# 14-Bit_ADC.net
KiCad netlist of a schematic drawn in Altium Designer
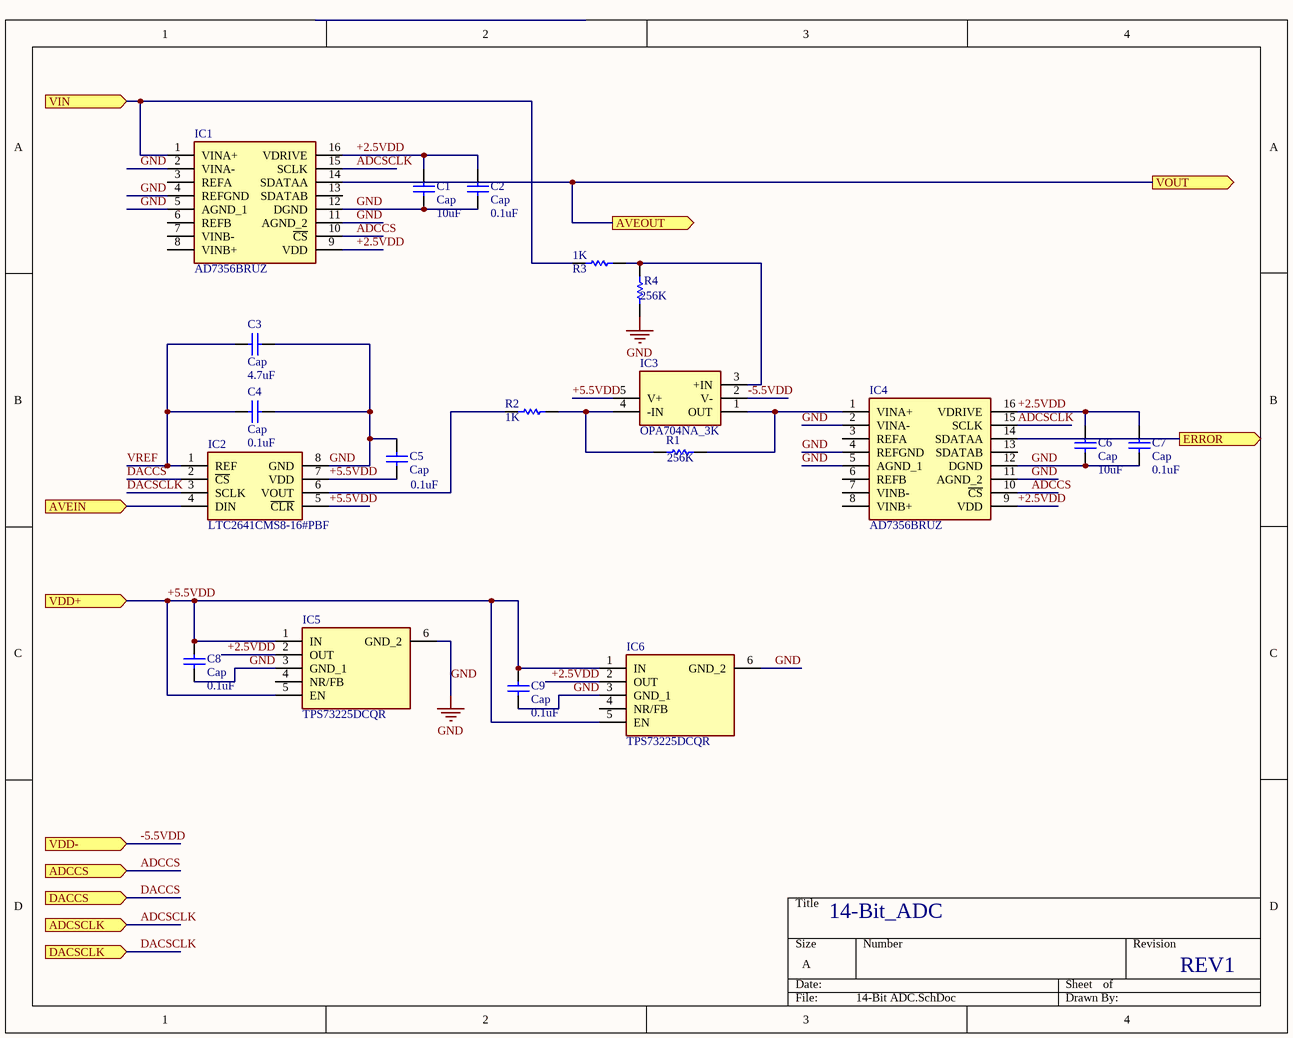
[diagram p0: 14-Bit ADC.SchDoc]

(export (version "E")
  (design (tool "Eeschema 10.0.6"))
  (components
    (comp (ref "C1")
      (value "Cap")
      (footprint "RAD-0.3")
      (description "Capacitor")
      (fields (field (name "ALTIUM_VALUE") "10uF") (field (name "PUBLISHER") "Altium Limited"))
      (libsource (lib "Miscellaneous Devices") (part "Cap"))
    )
    (comp (ref "C2")
      (value "Cap")
      (footprint "RAD-0.3")
      (description "Capacitor")
      (fields (field (name "ALTIUM_VALUE") "0.1uF") (field (name "PUBLISHER") "Altium Limited"))
      (libsource (lib "Miscellaneous Devices") (part "Cap"))
    )
    (comp (ref "C3")
      (value "Cap")
      (footprint "RAD-0.3")
      (description "Capacitor")
      (fields (field (name "ALTIUM_VALUE") "4.7uF") (field (name "PUBLISHER") "Altium Limited"))
      (libsource (lib "Miscellaneous Devices") (part "Cap"))
    )
    (comp (ref "C4")
      (value "Cap")
      (footprint "RAD-0.3")
      (description "Capacitor")
      (fields (field (name "ALTIUM_VALUE") "0.1uF") (field (name "PUBLISHER") "Altium Limited"))
      (libsource (lib "Miscellaneous Devices") (part "Cap"))
    )
    (comp (ref "C5")
      (value "Cap")
      (footprint "RAD-0.3")
      (description "Capacitor")
      (fields (field (name "ALTIUM_VALUE") "0.1uF") (field (name "PUBLISHER") "Altium Limited"))
      (libsource (lib "Miscellaneous Devices") (part "Cap"))
    )
    (comp (ref "C6")
      (value "Cap")
      (footprint "RAD-0.3")
      (description "Capacitor")
      (fields (field (name "ALTIUM_VALUE") "10uF") (field (name "PUBLISHER") "Altium Limited"))
      (libsource (lib "Miscellaneous Devices") (part "Cap"))
    )
    (comp (ref "C7")
      (value "Cap")
      (footprint "RAD-0.3")
      (description "Capacitor")
      (fields (field (name "ALTIUM_VALUE") "0.1uF") (field (name "PUBLISHER") "Altium Limited"))
      (libsource (lib "Miscellaneous Devices") (part "Cap"))
    )
    (comp (ref "C8")
      (value "Cap")
      (footprint "RAD-0.3")
      (description "Capacitor")
      (fields (field (name "ALTIUM_VALUE") "0.1uF") (field (name "PUBLISHER") "Altium Limited"))
      (libsource (lib "Miscellaneous Devices") (part "Cap"))
    )
    (comp (ref "C9")
      (value "Cap")
      (footprint "RAD-0.3")
      (description "Capacitor")
      (fields (field (name "ALTIUM_VALUE") "0.1uF") (field (name "PUBLISHER") "Altium Limited"))
      (libsource (lib "Miscellaneous Devices") (part "Cap"))
    )
    (comp (ref "IC1")
      (value "AD7356BRUZ")
      (footprint "SamacSys:SOP65P640X120-16N")
      (description "Integrated Circuit")
      (libsource (lib "*") (part "AD7356BRUZ"))
    )
    (comp (ref "IC2")
      (value "LTC2641CMS8-16#PBF")
      (footprint "SamacSys:SOP65P490X110-8N")
      (description "Integrated Circuit")
      (fields (field (name "MOUSER PART NUMBER") "584-C2641CMS8-16PBF"))
      (libsource (lib "*") (part "LTC2641CMS8-16#PBF"))
    )
    (comp (ref "IC3")
      (value "OPA704NA_3K")
      (footprint "SamacSys:SOT95P280X145-5N")
      (description "Integrated Circuit")
      (fields (field (name "MANUFACTURER_PART_NUMBER") "OPA704NA/3K"))
      (libsource (lib "*") (part "OPA704NA_3K"))
    )
    (comp (ref "IC4")
      (value "AD7356BRUZ")
      (footprint "SamacSys:SOP65P640X120-16N")
      (description "Integrated Circuit")
      (libsource (lib "*") (part "AD7356BRUZ"))
    )
    (comp (ref "IC5")
      (value "TPS73225DCQR")
      (footprint "SamacSys:SOT127P706X180-6N")
      (description "Integrated Circuit")
      (libsource (lib "*") (part "TPS73225DCQR"))
    )
    (comp (ref "IC6")
      (value "TPS73225DCQR")
      (footprint "SamacSys:SOT127P706X180-6N")
      (description "Integrated Circuit")
      (libsource (lib "*") (part "TPS73225DCQR"))
    )
    (comp (ref "R1")
      (value "256K")
      (footprint "AXIAL-0.3")
      (description "Resistor")
      (fields (field (name "PUBLISHER") "Altium Limited"))
      (libsource (lib "Miscellaneous Devices") (part "Res1"))
    )
    (comp (ref "R2")
      (value "1K")
      (footprint "AXIAL-0.3")
      (description "Resistor")
      (fields (field (name "PUBLISHER") "Altium Limited"))
      (libsource (lib "Miscellaneous Devices") (part "Res1"))
    )
    (comp (ref "R3")
      (value "1K")
      (footprint "AXIAL-0.3")
      (description "Resistor")
      (fields (field (name "PUBLISHER") "Altium Limited"))
      (libsource (lib "Miscellaneous Devices") (part "Res1"))
    )
    (comp (ref "R4")
      (value "256K")
      (footprint "AXIAL-0.3")
      (description "Resistor")
      (fields (field (name "PUBLISHER") "Altium Limited"))
      (libsource (lib "Miscellaneous Devices") (part "Res1"))
    )
  )
  (nets
    (net (code "1") (name "/+2.5VDD") (class "Default")
      (node (ref "C1") (pin "2") (pinfunction "2_2") (pintype "passive"))
      (node (ref "C2") (pin "2") (pinfunction "2_2") (pintype "passive"))
      (node (ref "C6") (pin "2") (pinfunction "2_2") (pintype "passive"))
      (node (ref "C7") (pin "2") (pinfunction "2_2") (pintype "passive"))
      (node (ref "IC1") (pin "16") (pinfunction "VDRIVE_16") (pintype "passive"))
      (node (ref "IC1") (pin "9") (pinfunction "VDD_9") (pintype "passive"))
      (node (ref "IC4") (pin "16") (pinfunction "VDRIVE_16") (pintype "passive"))
      (node (ref "IC4") (pin "9") (pinfunction "VDD_9") (pintype "passive"))
      (node (ref "IC5") (pin "2") (pinfunction "OUT_2") (pintype "passive"))
      (node (ref "IC6") (pin "2") (pinfunction "OUT_2") (pintype "passive"))
    )
    (net (code "2") (name "/+5.5VDD") (class "Default")
      (node (ref "C5") (pin "2") (pinfunction "2_2") (pintype "passive"))
      (node (ref "C8") (pin "1") (pinfunction "1_1") (pintype "passive"))
      (node (ref "C9") (pin "1") (pinfunction "1_1") (pintype "passive"))
      (node (ref "IC2") (pin "5") (pinfunction "~{CLR}_5") (pintype "passive"))
      (node (ref "IC2") (pin "7") (pinfunction "VDD_7") (pintype "passive"))
      (node (ref "IC3") (pin "5") (pinfunction "V+_5") (pintype "passive"))
      (node (ref "IC5") (pin "1") (pinfunction "IN_1") (pintype "passive"))
      (node (ref "IC5") (pin "5") (pinfunction "EN_5") (pintype "passive"))
      (node (ref "IC6") (pin "1") (pinfunction "IN_1") (pintype "passive"))
      (node (ref "IC6") (pin "5") (pinfunction "EN_5") (pintype "passive"))
    )
    (net (code "3") (name "/-5.5VDD") (class "Default")
      (node (ref "IC3") (pin "2") (pinfunction "V-_2") (pintype "passive"))
    )
    (net (code "4") (name "/ADCCS") (class "Default")
      (node (ref "IC1") (pin "10") (pinfunction "~{CS}_10") (pintype "passive"))
      (node (ref "IC4") (pin "10") (pinfunction "~{CS}_10") (pintype "passive"))
    )
    (net (code "5") (name "/ADCSCLK") (class "Default")
      (node (ref "IC1") (pin "15") (pinfunction "SCLK_15") (pintype "passive"))
      (node (ref "IC4") (pin "15") (pinfunction "SCLK_15") (pintype "passive"))
    )
    (net (code "6") (name "/AVEIN") (class "Default")
      (node (ref "IC2") (pin "4") (pinfunction "DIN_4") (pintype "passive"))
    )
    (net (code "7") (name "/AVEOUT") (class "Default")
      (node (ref "IC1") (pin "14") (pinfunction "SDATAA_14") (pintype "passive"))
    )
    (net (code "8") (name "/DACCS") (class "Default")
      (node (ref "IC2") (pin "2") (pinfunction "~{CS}_2") (pintype "passive"))
    )
    (net (code "9") (name "/DACSCLK") (class "Default")
      (node (ref "IC2") (pin "3") (pinfunction "SCLK_3") (pintype "passive"))
    )
    (net (code "10") (name "/ERROR") (class "Default")
      (node (ref "IC4") (pin "14") (pinfunction "SDATAA_14") (pintype "passive"))
    )
    (net (code "11") (name "/VIN") (class "Default")
      (node (ref "IC1") (pin "1") (pinfunction "VINA+_1") (pintype "passive"))
      (node (ref "R3") (pin "1") (pinfunction "1_1") (pintype "passive"))
    )
    (net (code "12") (name "/VREF") (class "Default")
      (node (ref "C3") (pin "1") (pinfunction "1_1") (pintype "passive"))
      (node (ref "C4") (pin "1") (pinfunction "1_1") (pintype "passive"))
      (node (ref "IC2") (pin "1") (pinfunction "REF_1") (pintype "passive"))
    )
    (net (code "13") (name "GND") (class "Default")
      (node (ref "C1") (pin "1") (pinfunction "1_1") (pintype "passive"))
      (node (ref "C2") (pin "1") (pinfunction "1_1") (pintype "passive"))
      (node (ref "C3") (pin "2") (pinfunction "2_2") (pintype "passive"))
      (node (ref "C4") (pin "2") (pinfunction "2_2") (pintype "passive"))
      (node (ref "C5") (pin "1") (pinfunction "1_1") (pintype "passive"))
      (node (ref "C6") (pin "1") (pinfunction "1_1") (pintype "passive"))
      (node (ref "C7") (pin "1") (pinfunction "1_1") (pintype "passive"))
      (node (ref "C8") (pin "2") (pinfunction "2_2") (pintype "passive"))
      (node (ref "C9") (pin "2") (pinfunction "2_2") (pintype "passive"))
      (node (ref "IC1") (pin "11") (pinfunction "AGND_2_11") (pintype "passive"))
      (node (ref "IC1") (pin "12") (pinfunction "DGND_12") (pintype "passive"))
      (node (ref "IC1") (pin "2") (pinfunction "VINA-_2") (pintype "passive"))
      (node (ref "IC1") (pin "4") (pinfunction "REFGND_4") (pintype "passive"))
      (node (ref "IC1") (pin "5") (pinfunction "AGND_1_5") (pintype "passive"))
      (node (ref "IC2") (pin "8") (pinfunction "GND_8") (pintype "passive"))
      (node (ref "IC4") (pin "11") (pinfunction "AGND_2_11") (pintype "passive"))
      (node (ref "IC4") (pin "12") (pinfunction "DGND_12") (pintype "passive"))
      (node (ref "IC4") (pin "2") (pinfunction "VINA-_2") (pintype "passive"))
      (node (ref "IC4") (pin "4") (pinfunction "REFGND_4") (pintype "passive"))
      (node (ref "IC4") (pin "5") (pinfunction "AGND_1_5") (pintype "passive"))
      (node (ref "IC5") (pin "3") (pinfunction "GND_1_3") (pintype "passive"))
      (node (ref "IC5") (pin "6") (pinfunction "GND_2_6") (pintype "passive"))
      (node (ref "IC6") (pin "3") (pinfunction "GND_1_3") (pintype "passive"))
      (node (ref "IC6") (pin "6") (pinfunction "GND_2_6") (pintype "passive"))
      (node (ref "R4") (pin "1") (pinfunction "1_1") (pintype "passive"))
    )
    (net (code "14") (name "Net-(IC2-VOUT)") (class "Default")
      (node (ref "IC2") (pin "6") (pinfunction "VOUT_6") (pintype "passive"))
      (node (ref "R2") (pin "1") (pinfunction "1_1") (pintype "passive"))
    )
    (net (code "15") (name "Net-(IC3-+IN)") (class "Default")
      (node (ref "IC3") (pin "3") (pinfunction "+IN_3") (pintype "passive"))
      (node (ref "R3") (pin "2") (pinfunction "2_2") (pintype "passive"))
      (node (ref "R4") (pin "2") (pinfunction "2_2") (pintype "passive"))
    )
    (net (code "16") (name "Net-(IC3--IN)") (class "Default")
      (node (ref "IC3") (pin "4") (pinfunction "-IN_4") (pintype "passive"))
      (node (ref "R1") (pin "1") (pinfunction "1_1") (pintype "passive"))
      (node (ref "R2") (pin "2") (pinfunction "2_2") (pintype "passive"))
    )
    (net (code "17") (name "Net-(IC3-OUT)") (class "Default")
      (node (ref "IC3") (pin "1") (pinfunction "OUT_1") (pintype "passive"))
      (node (ref "IC4") (pin "1") (pinfunction "VINA+_1") (pintype "passive"))
      (node (ref "R1") (pin "2") (pinfunction "2_2") (pintype "passive"))
    )
    (net (code "18") (name "unconnected-(IC1-REFA-Pad3)") (class "Default")
      (node (ref "IC1") (pin "3") (pinfunction "REFA_3") (pintype "passive"))
    )
    (net (code "19") (name "unconnected-(IC1-REFB-Pad6)") (class "Default")
      (node (ref "IC1") (pin "6") (pinfunction "REFB_6") (pintype "passive"))
    )
    (net (code "20") (name "unconnected-(IC1-SDATAB-Pad13)") (class "Default")
      (node (ref "IC1") (pin "13") (pinfunction "SDATAB_13") (pintype "passive"))
    )
    (net (code "21") (name "unconnected-(IC1-VINB+-Pad8)") (class "Default")
      (node (ref "IC1") (pin "8") (pinfunction "VINB+_8") (pintype "passive"))
    )
    (net (code "22") (name "unconnected-(IC1-VINB--Pad7)") (class "Default")
      (node (ref "IC1") (pin "7") (pinfunction "VINB-_7") (pintype "passive"))
    )
    (net (code "23") (name "unconnected-(IC4-REFA-Pad3)") (class "Default")
      (node (ref "IC4") (pin "3") (pinfunction "REFA_3") (pintype "passive"))
    )
    (net (code "24") (name "unconnected-(IC4-REFB-Pad6)") (class "Default")
      (node (ref "IC4") (pin "6") (pinfunction "REFB_6") (pintype "passive"))
    )
    (net (code "25") (name "unconnected-(IC4-SDATAB-Pad13)") (class "Default")
      (node (ref "IC4") (pin "13") (pinfunction "SDATAB_13") (pintype "passive"))
    )
    (net (code "26") (name "unconnected-(IC4-VINB+-Pad8)") (class "Default")
      (node (ref "IC4") (pin "8") (pinfunction "VINB+_8") (pintype "passive"))
    )
    (net (code "27") (name "unconnected-(IC4-VINB--Pad7)") (class "Default")
      (node (ref "IC4") (pin "7") (pinfunction "VINB-_7") (pintype "passive"))
    )
    (net (code "28") (name "unconnected-(IC5-NR{slash}FB-Pad4)") (class "Default")
      (node (ref "IC5") (pin "4") (pinfunction "NR/FB_4") (pintype "passive"))
    )
    (net (code "29") (name "unconnected-(IC6-NR{slash}FB-Pad4)") (class "Default")
      (node (ref "IC6") (pin "4") (pinfunction "NR/FB_4") (pintype "passive"))
    )
  )
)
